# zeta2rework_lw_v19.net
KiCad netlist of a schematic drawn in EAGLE
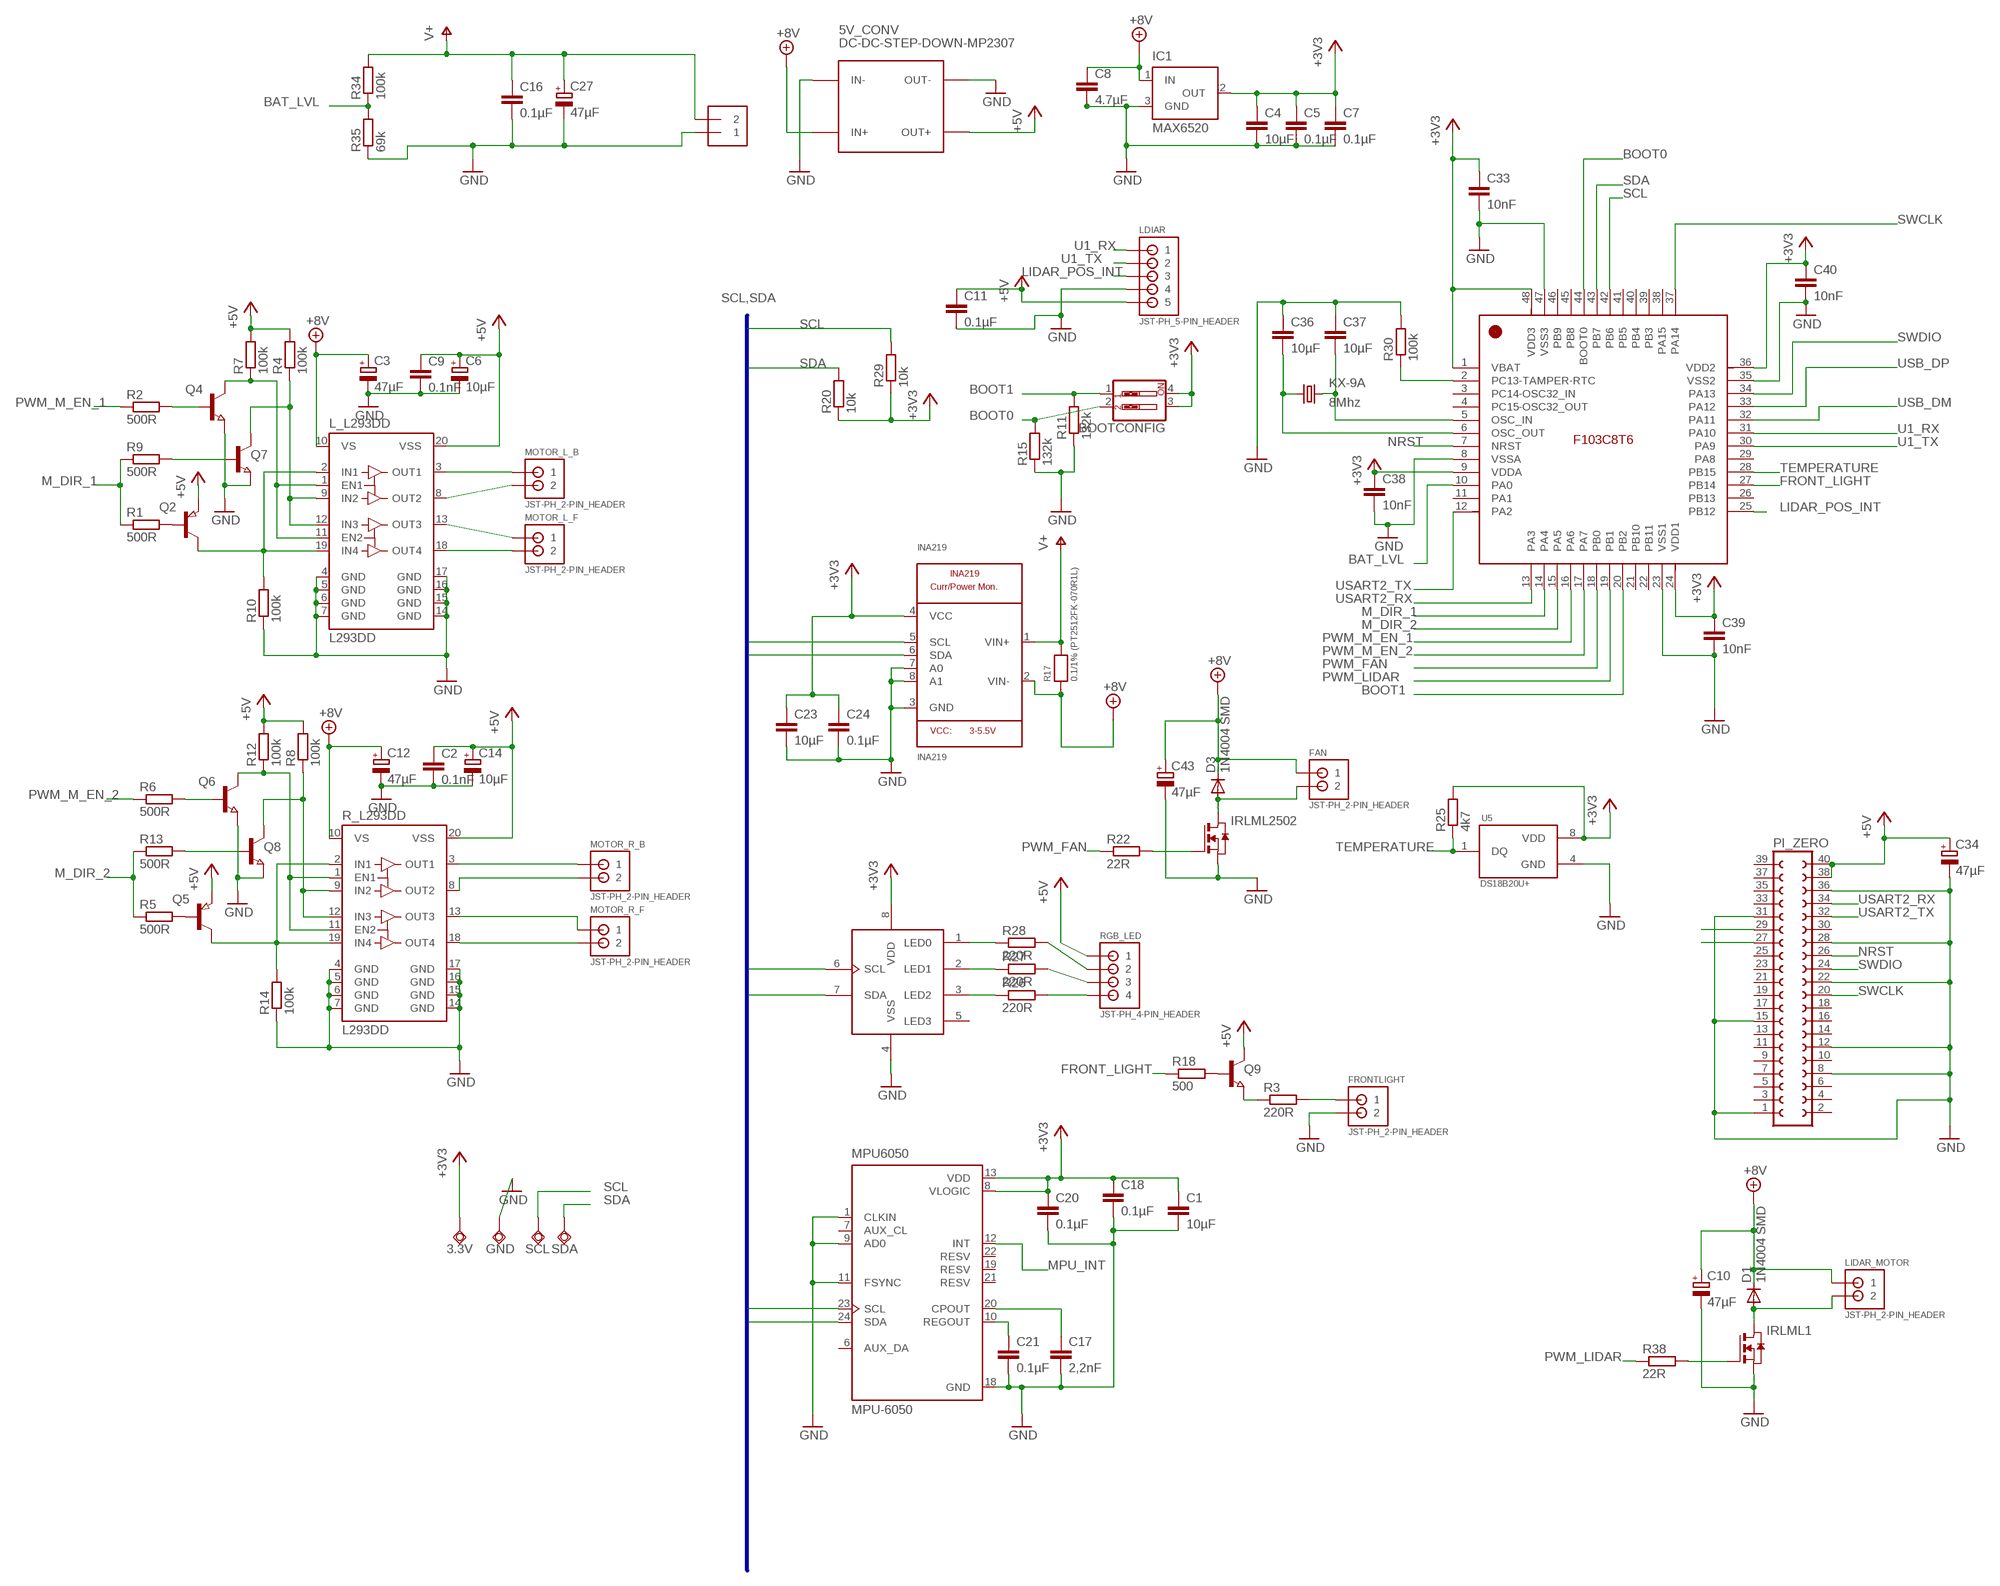
[diagram p0: schematic, sheet 1]

(export (version "E")
  (design (tool "Eeschema 10.0.6"))
  (components
    (comp (ref "3.3V")
      (value "TPSQTP20R")
      (footprint "eagle-import:TP20R")
      (libsource (lib "eagle-import") (part "TPSQTP20R"))
    )
    (comp (ref "5V_CONV")
      (value "DC-DC-STEP-DOWN-MP2307")
      (footprint "eagle-import:DC-DC-STEP-DOWN-MP2307")
      (libsource (lib "eagle-import") (part "DC-DC-STEP-DOWN-MP2307"))
    )
    (comp (ref "BOOTCONFIG")
      (value "SW_DIP-2")
      (footprint "eagle-import:EDG-02")
      (libsource (lib "eagle-import") (part "SW_DIP-2"))
    )
    (comp (ref "C1")
      (value "10µF")
      (footprint "eagle-import:C1206")
      (libsource (lib "eagle-import") (part "C-EUC1206"))
    )
    (comp (ref "C2")
      (value "0.1nF")
      (footprint "eagle-import:C1206")
      (libsource (lib "eagle-import") (part "C-EUC1206"))
    )
    (comp (ref "C3")
      (value "47µF")
      (footprint "eagle-import:UD-4X5,8_NICHICON")
      (libsource (lib "eagle-import") (part "CPOL-EUUD-4X5,8"))
    )
    (comp (ref "C4")
      (value "10µF")
      (footprint "eagle-import:C1206")
      (libsource (lib "eagle-import") (part "C-EUC1206"))
    )
    (comp (ref "C5")
      (value "0.1µF")
      (footprint "eagle-import:C1206")
      (libsource (lib "eagle-import") (part "C-EUC1206"))
    )
    (comp (ref "C6")
      (value "10µF")
      (footprint "eagle-import:UD-4X5,8_NICHICON")
      (libsource (lib "eagle-import") (part "CPOL-EUUD-4X5,8"))
    )
    (comp (ref "C7")
      (value "0.1µF")
      (footprint "eagle-import:C1206")
      (libsource (lib "eagle-import") (part "C-EUC1206"))
    )
    (comp (ref "C8")
      (value "4.7µF")
      (footprint "eagle-import:C1206")
      (libsource (lib "eagle-import") (part "C-EUC1206"))
    )
    (comp (ref "C9")
      (value "0.1nF")
      (footprint "eagle-import:C1206")
      (libsource (lib "eagle-import") (part "C-EUC1206"))
    )
    (comp (ref "C10")
      (value "47µF")
      (footprint "eagle-import:UD-4X5,8_NICHICON")
      (libsource (lib "eagle-import") (part "CPOL-EUUD-4X5,8"))
    )
    (comp (ref "C11")
      (value "0.1µF")
      (footprint "eagle-import:C1206")
      (libsource (lib "eagle-import") (part "C-EUC1206"))
    )
    (comp (ref "C12")
      (value "47µF")
      (footprint "eagle-import:UD-4X5,8_NICHICON")
      (libsource (lib "eagle-import") (part "CPOL-EUUD-4X5,8"))
    )
    (comp (ref "C14")
      (value "10µF")
      (footprint "eagle-import:UD-4X5,8_NICHICON")
      (libsource (lib "eagle-import") (part "CPOL-EUUD-4X5,8"))
    )
    (comp (ref "C16")
      (value "0.1µF")
      (footprint "eagle-import:C1206")
      (libsource (lib "eagle-import") (part "C-EUC1206"))
    )
    (comp (ref "C17")
      (value "2,2nF")
      (footprint "eagle-import:C1206")
      (libsource (lib "eagle-import") (part "C-EUC1206"))
    )
    (comp (ref "C18")
      (value "0.1µF")
      (footprint "eagle-import:C1206")
      (libsource (lib "eagle-import") (part "C-EUC1206"))
    )
    (comp (ref "C20")
      (value "0.1µF")
      (footprint "eagle-import:C1206")
      (libsource (lib "eagle-import") (part "C-EUC1206"))
    )
    (comp (ref "C21")
      (value "0.1µF")
      (footprint "eagle-import:C1206")
      (libsource (lib "eagle-import") (part "C-EUC1206"))
    )
    (comp (ref "C23")
      (value "10µF")
      (footprint "eagle-import:C1206")
      (libsource (lib "eagle-import") (part "C-EUC1206"))
    )
    (comp (ref "C24")
      (value "0.1µF")
      (footprint "eagle-import:C1206")
      (libsource (lib "eagle-import") (part "C-EUC1206"))
    )
    (comp (ref "C27")
      (value "47µF")
      (footprint "eagle-import:UD-4X5,8_NICHICON")
      (libsource (lib "eagle-import") (part "CPOL-EUUD-4X5,8"))
    )
    (comp (ref "C33")
      (value "10nF")
      (footprint "eagle-import:C1206")
      (libsource (lib "eagle-import") (part "C-EUC1206"))
    )
    (comp (ref "C34")
      (value "47µF")
      (footprint "eagle-import:UD-4X5,8_NICHICON")
      (libsource (lib "eagle-import") (part "CPOL-EUUD-4X5,8"))
    )
    (comp (ref "C36")
      (value "10µF")
      (footprint "eagle-import:C1206")
      (libsource (lib "eagle-import") (part "C-EUC1206"))
    )
    (comp (ref "C37")
      (value "10µF")
      (footprint "eagle-import:C1206")
      (libsource (lib "eagle-import") (part "C-EUC1206"))
    )
    (comp (ref "C38")
      (value "10nF")
      (footprint "eagle-import:C1206")
      (libsource (lib "eagle-import") (part "C-EUC1206"))
    )
    (comp (ref "C39")
      (value "10nF")
      (footprint "eagle-import:C1206")
      (libsource (lib "eagle-import") (part "C-EUC1206"))
    )
    (comp (ref "C40")
      (value "10nF")
      (footprint "eagle-import:C1206")
      (libsource (lib "eagle-import") (part "C-EUC1206"))
    )
    (comp (ref "C43")
      (value "47µF")
      (footprint "eagle-import:UD-4X5,8_NICHICON")
      (libsource (lib "eagle-import") (part "CPOL-EUUD-4X5,8"))
    )
    (comp (ref "D1")
      (value "1N4004 SMD")
      (footprint "eagle-import:DO214AC")
      (libsource (lib "eagle-import") (part "DIODE-DO214AC"))
    )
    (comp (ref "D3")
      (value "1N4004 SMD")
      (footprint "eagle-import:DO214AC")
      (libsource (lib "eagle-import") (part "DIODE-DO214AC"))
    )
    (comp (ref "FAN")
      (value "JST-PH_2-PIN_HEADER")
      (footprint "eagle-import:JST_B2B-PH_HEADER")
      (libsource (lib "eagle-import") (part "JST-PH_2-PIN_HEADER"))
    )
    (comp (ref "FRONTLIGHT")
      (value "JST-PH_2-PIN_HEADER")
      (footprint "eagle-import:JST_B2B-PH_HEADER")
      (libsource (lib "eagle-import") (part "JST-PH_2-PIN_HEADER"))
    )
    (comp (ref "GND")
      (value "TPSQTP20R")
      (footprint "eagle-import:TP20R")
      (libsource (lib "eagle-import") (part "TPSQTP20R"))
    )
    (comp (ref "IC1")
      (value "MAX6520")
      (footprint "eagle-import:SOT23")
      (fields (field (name "MF") "MAXIM") (field (name "MPN") "MAX6520EUR-T"))
      (libsource (lib "eagle-import") (part "MAX6520"))
    )
    (comp (ref "INA219")
      (value "INA219")
      (footprint "eagle-import:SOT23-8")
      (fields (field (name "MF") "Texas Instruments"))
      (libsource (lib "eagle-import") (part "INA219"))
    )
    (comp (ref "IRLML1")
      (value "NMOSSOT23")
      (footprint "eagle-import:SOT-23")
      (libsource (lib "eagle-import") (part "NMOSSOT23"))
    )
    (comp (ref "IRLML2502")
      (value "NMOSSOT23")
      (footprint "eagle-import:SOT-23")
      (libsource (lib "eagle-import") (part "NMOSSOT23"))
    )
    (comp (ref "KX-9A")
      (value "8Mhz")
      (footprint "eagle-import:5.0X3.2_KX-9A")
      (libsource (lib "eagle-import") (part "KX-9A"))
    )
    (comp (ref "LDIAR")
      (value "JST-PH_5-PIN_HEADER")
      (footprint "eagle-import:JST_B5B-PH_HEADER")
      (libsource (lib "eagle-import") (part "JST-PH_5-PIN_HEADER"))
    )
    (comp (ref "LIDAR_MOTOR")
      (value "JST-PH_2-PIN_HEADER")
      (footprint "eagle-import:JST_B2B-PH_HEADER")
      (libsource (lib "eagle-import") (part "JST-PH_2-PIN_HEADER"))
    )
    (comp (ref "LIPO_2S")
      (value "TERMBLOCK_1X2-3.5MM")
      (footprint "eagle-import:1X2-3.5MM")
      (libsource (lib "eagle-import") (part "TERMBLOCK_1X2-3.5MM"))
    )
    (comp (ref "L_L293DD")
      (value "L293DD")
      (footprint "eagle-import:SO20")
      (libsource (lib "eagle-import") (part "L293DD"))
    )
    (comp (ref "MOTOR_L_B")
      (value "JST-PH_2-PIN_HEADER")
      (footprint "eagle-import:JST_B2B-PH_HEADER")
      (libsource (lib "eagle-import") (part "JST-PH_2-PIN_HEADER"))
    )
    (comp (ref "MOTOR_L_F")
      (value "JST-PH_2-PIN_HEADER")
      (footprint "eagle-import:JST_B2B-PH_HEADER")
      (libsource (lib "eagle-import") (part "JST-PH_2-PIN_HEADER"))
    )
    (comp (ref "MOTOR_R_B")
      (value "JST-PH_2-PIN_HEADER")
      (footprint "eagle-import:JST_B2B-PH_HEADER")
      (libsource (lib "eagle-import") (part "JST-PH_2-PIN_HEADER"))
    )
    (comp (ref "MOTOR_R_F")
      (value "JST-PH_2-PIN_HEADER")
      (footprint "eagle-import:JST_B2B-PH_HEADER")
      (libsource (lib "eagle-import") (part "JST-PH_2-PIN_HEADER"))
    )
    (comp (ref "MPU6050")
      (value "MPU-6050")
      (footprint "eagle-import:QFN50P400X400X95-24N")
      (fields (field (name "MF") "TDK"))
      (libsource (lib "eagle-import") (part "MPU-6050"))
    )
    (comp (ref "PCA9533")
      (value "PCA9533")
      (footprint "eagle-import:SOIC8")
      (libsource (lib "eagle-import") (part "PCA9533"))
    )
    (comp (ref "PI_ZERO")
      (value "FE20-2")
      (footprint "eagle-import:FE20-2")
      (libsource (lib "eagle-import") (part "FE20-2"))
    )
    (comp (ref "Q2")
      (value "PNP-TRANSISTOR_SOT23")
      (footprint "eagle-import:SOT23")
      (libsource (lib "eagle-import") (part "PNP-TRANSISTOR_SOT23"))
    )
    (comp (ref "Q4")
      (value "NPN-TRANSISTOR_SOT23")
      (footprint "eagle-import:SOT23")
      (libsource (lib "eagle-import") (part "NPN-TRANSISTOR_SOT23"))
    )
    (comp (ref "Q5")
      (value "PNP-TRANSISTOR_SOT23")
      (footprint "eagle-import:SOT23")
      (libsource (lib "eagle-import") (part "PNP-TRANSISTOR_SOT23"))
    )
    (comp (ref "Q6")
      (value "NPN-TRANSISTOR_SOT23")
      (footprint "eagle-import:SOT23")
      (libsource (lib "eagle-import") (part "NPN-TRANSISTOR_SOT23"))
    )
    (comp (ref "Q7")
      (value "NPN-TRANSISTOR_SOT23")
      (footprint "eagle-import:SOT23")
      (libsource (lib "eagle-import") (part "NPN-TRANSISTOR_SOT23"))
    )
    (comp (ref "Q8")
      (value "NPN-TRANSISTOR_SOT23")
      (footprint "eagle-import:SOT23")
      (libsource (lib "eagle-import") (part "NPN-TRANSISTOR_SOT23"))
    )
    (comp (ref "Q9")
      (value "NPN-TRANSISTOR_SOT23")
      (footprint "eagle-import:SOT23")
      (libsource (lib "eagle-import") (part "NPN-TRANSISTOR_SOT23"))
    )
    (comp (ref "R1")
      (value "500R")
      (footprint "eagle-import:R0603")
      (libsource (lib "eagle-import") (part "R-EU_R0603"))
    )
    (comp (ref "R2")
      (value "500R")
      (footprint "eagle-import:R0603")
      (libsource (lib "eagle-import") (part "R-EU_R0603"))
    )
    (comp (ref "R3")
      (value "220R")
      (footprint "eagle-import:R0603")
      (libsource (lib "eagle-import") (part "R-EU_R0603"))
    )
    (comp (ref "R4")
      (value "100k")
      (footprint "eagle-import:R0603")
      (libsource (lib "eagle-import") (part "R-EU_R0603"))
    )
    (comp (ref "R5")
      (value "500R")
      (footprint "eagle-import:R0603")
      (libsource (lib "eagle-import") (part "R-EU_R0603"))
    )
    (comp (ref "R6")
      (value "500R")
      (footprint "eagle-import:R0603")
      (libsource (lib "eagle-import") (part "R-EU_R0603"))
    )
    (comp (ref "R7")
      (value "100k")
      (footprint "eagle-import:R0603")
      (libsource (lib "eagle-import") (part "R-EU_R0603"))
    )
    (comp (ref "R8")
      (value "100k")
      (footprint "eagle-import:R0603")
      (libsource (lib "eagle-import") (part "R-EU_R0603"))
    )
    (comp (ref "R9")
      (value "500R")
      (footprint "eagle-import:R0603")
      (libsource (lib "eagle-import") (part "R-EU_R0603"))
    )
    (comp (ref "R10")
      (value "100k")
      (footprint "eagle-import:R0603")
      (libsource (lib "eagle-import") (part "R-EU_R0603"))
    )
    (comp (ref "R11")
      (value "132k")
      (footprint "eagle-import:R0603")
      (libsource (lib "eagle-import") (part "R-EU_R0603"))
    )
    (comp (ref "R12")
      (value "100k")
      (footprint "eagle-import:R0603")
      (libsource (lib "eagle-import") (part "R-EU_R0603"))
    )
    (comp (ref "R13")
      (value "500R")
      (footprint "eagle-import:R0603")
      (libsource (lib "eagle-import") (part "R-EU_R0603"))
    )
    (comp (ref "R14")
      (value "100k")
      (footprint "eagle-import:R0603")
      (libsource (lib "eagle-import") (part "R-EU_R0603"))
    )
    (comp (ref "R15")
      (value "132k")
      (footprint "eagle-import:R0603")
      (libsource (lib "eagle-import") (part "R-EU_R0603"))
    )
    (comp (ref "R17")
      (value "0.1/1% (PT2512FK-070R1L)")
      (footprint "eagle-import:2512")
      (libsource (lib "eagle-import") (part "RESISTOR2512"))
    )
    (comp (ref "R18")
      (value "500")
      (footprint "eagle-import:R1206")
      (libsource (lib "eagle-import") (part "R-EU_R1206"))
    )
    (comp (ref "R20")
      (value "10k")
      (footprint "eagle-import:R0603")
      (libsource (lib "eagle-import") (part "R-EU_R0603"))
    )
    (comp (ref "R22")
      (value "22R")
      (footprint "eagle-import:R0603")
      (libsource (lib "eagle-import") (part "R-EU_R0603"))
    )
    (comp (ref "R25")
      (value "4k7")
      (footprint "eagle-import:R0603")
      (libsource (lib "eagle-import") (part "R-EU_R0603"))
    )
    (comp (ref "R26")
      (value "220R")
      (footprint "eagle-import:R0603")
      (libsource (lib "eagle-import") (part "R-EU_R0603"))
    )
    (comp (ref "R27")
      (value "220R")
      (footprint "eagle-import:R0603")
      (libsource (lib "eagle-import") (part "R-EU_R0603"))
    )
    (comp (ref "R28")
      (value "220R")
      (footprint "eagle-import:R0603")
      (libsource (lib "eagle-import") (part "R-EU_R0603"))
    )
    (comp (ref "R29")
      (value "10k")
      (footprint "eagle-import:R0603")
      (libsource (lib "eagle-import") (part "R-EU_R0603"))
    )
    (comp (ref "R30")
      (value "100k")
      (footprint "eagle-import:R0603")
      (libsource (lib "eagle-import") (part "R-EU_R0603"))
    )
    (comp (ref "R34")
      (value "100k")
      (footprint "eagle-import:R0603")
      (libsource (lib "eagle-import") (part "R-EU_R0603"))
    )
    (comp (ref "R35")
      (value "69k")
      (footprint "eagle-import:R0603")
      (libsource (lib "eagle-import") (part "R-EU_R0603"))
    )
    (comp (ref "R38")
      (value "22R")
      (footprint "eagle-import:R0603")
      (libsource (lib "eagle-import") (part "R-EU_R0603"))
    )
    (comp (ref "RGB_LED")
      (value "JST-PH_4-PIN_HEADER")
      (footprint "eagle-import:JST_B4B-PH_HEADER")
      (libsource (lib "eagle-import") (part "JST-PH_4-PIN_HEADER"))
    )
    (comp (ref "R_L293DD")
      (value "L293DD")
      (footprint "eagle-import:SO20")
      (libsource (lib "eagle-import") (part "L293DD"))
    )
    (comp (ref "SCL")
      (value "TPSQTP20R")
      (footprint "eagle-import:TP20R")
      (libsource (lib "eagle-import") (part "TPSQTP20R"))
    )
    (comp (ref "SDA")
      (value "TPSQTP20R")
      (footprint "eagle-import:TP20R")
      (libsource (lib "eagle-import") (part "TPSQTP20R"))
    )
    (comp (ref "STM32F103CB")
      (value "STM32F103CB")
      (footprint "eagle-import:LQFP48_7X7MM_0.5MMPP")
      (fields (field (name "MF") "STMicroelectronics") (field (name "MP") "STM32F103C8T6"))
      (libsource (lib "eagle-import") (part "STM32F103C8T6"))
    )
    (comp (ref "U5")
      (value "DS18B20U+")
      (footprint "eagle-import:SOP65P490X95-8N")
      (fields (field (name "MF") "Maxim"))
      (libsource (lib "eagle-import") (part "DS18B20U+"))
    )
  )
  (nets
    (net (code "1") (name "+3V3") (class "Default")
      (node (ref "3.3V") (pin "TP") (pinfunction "TP_TP") (pintype "input"))
      (node (ref "BOOTCONFIG") (pin "3") (pinfunction "3_3") (pintype "passive"))
      (node (ref "BOOTCONFIG") (pin "4") (pinfunction "4_4") (pintype "passive"))
      (node (ref "C1") (pin "1") (pinfunction "1_1") (pintype "passive"))
      (node (ref "C18") (pin "1") (pinfunction "1_1") (pintype "passive"))
      (node (ref "C20") (pin "1") (pinfunction "1_1") (pintype "passive"))
      (node (ref "C23") (pin "1") (pinfunction "1_1") (pintype "passive"))
      (node (ref "C24") (pin "1") (pinfunction "1_1") (pintype "passive"))
      (node (ref "C33") (pin "1") (pinfunction "1_1") (pintype "passive"))
      (node (ref "C38") (pin "1") (pinfunction "1_1") (pintype "passive"))
      (node (ref "C39") (pin "1") (pinfunction "1_1") (pintype "passive"))
      (node (ref "C4") (pin "1") (pinfunction "1_1") (pintype "passive"))
      (node (ref "C40") (pin "1") (pinfunction "1_1") (pintype "passive"))
      (node (ref "C5") (pin "1") (pinfunction "1_1") (pintype "passive"))
      (node (ref "C7") (pin "1") (pinfunction "1_1") (pintype "passive"))
      (node (ref "IC1") (pin "2") (pinfunction "OUT_2") (pintype "output"))
      (node (ref "INA219") (pin "4") (pinfunction "VCC_4") (pintype "bidirectional"))
      (node (ref "MPU6050") (pin "13") (pinfunction "VDD_13") (pintype "power_in"))
      (node (ref "MPU6050") (pin "8") (pinfunction "VLOGIC_8") (pintype "power_in"))
      (node (ref "PCA9533") (pin "8") (pinfunction "VDD_8") (pintype "power_in"))
      (node (ref "R20") (pin "1") (pinfunction "1_1") (pintype "passive"))
      (node (ref "R25") (pin "2") (pinfunction "2_2") (pintype "passive"))
      (node (ref "R29") (pin "1") (pinfunction "1_1") (pintype "passive"))
      (node (ref "STM32F103CB") (pin "1") (pinfunction "VBAT_1") (pintype "bidirectional"))
      (node (ref "STM32F103CB") (pin "24") (pinfunction "VDD1_24") (pintype "bidirectional"))
      (node (ref "STM32F103CB") (pin "36") (pinfunction "VDD2_36") (pintype "bidirectional"))
      (node (ref "STM32F103CB") (pin "48") (pinfunction "VDD3_48") (pintype "bidirectional"))
      (node (ref "STM32F103CB") (pin "9") (pinfunction "VDDA_9") (pintype "bidirectional"))
      (node (ref "U5") (pin "8") (pinfunction "VDD_8") (pintype "power_in"))
    )
    (net (code "2") (name "+5V") (class "Default")
      (node (ref "5V_CONV") (pin "OUT+") (pinfunction "OUT+_OUT+") (pintype "bidirectional"))
      (node (ref "C11") (pin "1") (pinfunction "1_1") (pintype "passive"))
      (node (ref "C14") (pin "+") (pinfunction "+_+") (pintype "passive"))
      (node (ref "C2") (pin "1") (pinfunction "1_1") (pintype "passive"))
      (node (ref "C34") (pin "+") (pinfunction "+_+") (pintype "passive"))
      (node (ref "C6") (pin "+") (pinfunction "+_+") (pintype "passive"))
      (node (ref "C9") (pin "1") (pinfunction "1_1") (pintype "passive"))
      (node (ref "LDIAR") (pin "P5") (pinfunction "5_P5") (pintype "bidirectional"))
      (node (ref "L_L293DD") (pin "20") (pinfunction "VSS_20") (pintype "power_in"))
      (node (ref "PI_ZERO") (pin "38") (pinfunction "38_38") (pintype "passive"))
      (node (ref "PI_ZERO") (pin "40") (pinfunction "40_40") (pintype "passive"))
      (node (ref "Q2") (pin "2") (pinfunction "E_2") (pintype "passive"))
      (node (ref "Q5") (pin "2") (pinfunction "E_2") (pintype "passive"))
      (node (ref "Q9") (pin "3") (pinfunction "C_3") (pintype "passive"))
      (node (ref "R12") (pin "2") (pinfunction "2_2") (pintype "passive"))
      (node (ref "R4") (pin "2") (pinfunction "2_2") (pintype "passive"))
      (node (ref "R7") (pin "2") (pinfunction "2_2") (pintype "passive"))
      (node (ref "R8") (pin "2") (pinfunction "2_2") (pintype "passive"))
      (node (ref "RGB_LED") (pin "P1") (pinfunction "1_P1") (pintype "bidirectional"))
      (node (ref "R_L293DD") (pin "20") (pinfunction "VSS_20") (pintype "power_in"))
    )
    (net (code "3") (name "+8V") (class "Default")
      (node (ref "5V_CONV") (pin "IN+") (pinfunction "IN+_IN+") (pintype "bidirectional"))
      (node (ref "C10") (pin "+") (pinfunction "+_+") (pintype "passive"))
      (node (ref "C12") (pin "+") (pinfunction "+_+") (pintype "passive"))
      (node (ref "C3") (pin "+") (pinfunction "+_+") (pintype "passive"))
      (node (ref "C43") (pin "+") (pinfunction "+_+") (pintype "passive"))
      (node (ref "C8") (pin "1") (pinfunction "1_1") (pintype "passive"))
      (node (ref "D1") (pin "C") (pinfunction "C_C") (pintype "passive"))
      (node (ref "D3") (pin "C") (pinfunction "C_C") (pintype "passive"))
      (node (ref "FAN") (pin "P1") (pinfunction "1_P1") (pintype "bidirectional"))
      (node (ref "IC1") (pin "1") (pinfunction "IN_1") (pintype "input"))
      (node (ref "INA219") (pin "2") (pinfunction "VIN-_2") (pintype "bidirectional"))
      (node (ref "LIDAR_MOTOR") (pin "P1") (pinfunction "1_P1") (pintype "bidirectional"))
      (node (ref "L_L293DD") (pin "10") (pinfunction "VS_10") (pintype "power_in"))
      (node (ref "R17") (pin "1") (pinfunction "1_1") (pintype "passive"))
      (node (ref "R_L293DD") (pin "10") (pinfunction "VS_10") (pintype "power_in"))
    )
    (net (code "4") (name "/BAT_LVL") (class "Default")
      (node (ref "R34") (pin "1") (pinfunction "1_1") (pintype "passive"))
      (node (ref "R35") (pin "2") (pinfunction "2_2") (pintype "passive"))
      (node (ref "STM32F103CB") (pin "10") (pinfunction "PA0_10") (pintype "bidirectional"))
    )
    (net (code "5") (name "/BOOT0") (class "Default")
      (node (ref "BOOTCONFIG") (pin "2") (pinfunction "2_2") (pintype "passive"))
      (node (ref "R15") (pin "2") (pinfunction "2_2") (pintype "passive"))
      (node (ref "STM32F103CB") (pin "44") (pinfunction "BOOT0_44") (pintype "bidirectional"))
    )
    (net (code "6") (name "/BOOT1") (class "Default")
      (node (ref "BOOTCONFIG") (pin "1") (pinfunction "1_1") (pintype "passive"))
      (node (ref "R11") (pin "2") (pinfunction "2_2") (pintype "passive"))
      (node (ref "STM32F103CB") (pin "20") (pinfunction "PB2_20") (pintype "bidirectional"))
    )
    (net (code "7") (name "/FRONT_LIGHT") (class "Default")
      (node (ref "R18") (pin "1") (pinfunction "1_1") (pintype "passive"))
      (node (ref "STM32F103CB") (pin "27") (pinfunction "PB14_27") (pintype "bidirectional"))
    )
    (net (code "8") (name "/LIDAR_POS_INT") (class "Default")
      (node (ref "LDIAR") (pin "P3") (pinfunction "3_P3") (pintype "bidirectional"))
      (node (ref "STM32F103CB") (pin "25") (pinfunction "PB12_25") (pintype "bidirectional"))
    )
    (net (code "9") (name "/MPU_INT") (class "Default")
      (node (ref "MPU6050") (pin "12") (pinfunction "INT_12") (pintype "output"))
    )
    (net (code "10") (name "/M_DIR_1") (class "Default")
      (node (ref "R1") (pin "1") (pinfunction "1_1") (pintype "passive"))
      (node (ref "R9") (pin "1") (pinfunction "1_1") (pintype "passive"))
      (node (ref "STM32F103CB") (pin "14") (pinfunction "PA4_14") (pintype "bidirectional"))
    )
    (net (code "11") (name "/M_DIR_2") (class "Default")
      (node (ref "R13") (pin "1") (pinfunction "1_1") (pintype "passive"))
      (node (ref "R5") (pin "1") (pinfunction "1_1") (pintype "passive"))
      (node (ref "STM32F103CB") (pin "15") (pinfunction "PA5_15") (pintype "bidirectional"))
    )
    (net (code "12") (name "/NRST") (class "Default")
      (node (ref "PI_ZERO") (pin "26") (pinfunction "26_26") (pintype "passive"))
      (node (ref "STM32F103CB") (pin "7") (pinfunction "NRST_7") (pintype "bidirectional"))
    )
    (net (code "13") (name "/PWM_FAN") (class "Default")
      (node (ref "R22") (pin "1") (pinfunction "1_1") (pintype "passive"))
      (node (ref "STM32F103CB") (pin "18") (pinfunction "PB0_18") (pintype "bidirectional"))
    )
    (net (code "14") (name "/PWM_LIDAR") (class "Default")
      (node (ref "R38") (pin "1") (pinfunction "1_1") (pintype "passive"))
      (node (ref "STM32F103CB") (pin "19") (pinfunction "PB1_19") (pintype "bidirectional"))
    )
    (net (code "15") (name "/PWM_M_EN_1") (class "Default")
      (node (ref "R2") (pin "1") (pinfunction "1_1") (pintype "passive"))
      (node (ref "STM32F103CB") (pin "16") (pinfunction "PA6_16") (pintype "bidirectional"))
    )
    (net (code "16") (name "/PWM_M_EN_2") (class "Default")
      (node (ref "R6") (pin "1") (pinfunction "1_1") (pintype "passive"))
      (node (ref "STM32F103CB") (pin "17") (pinfunction "PA7_17") (pintype "bidirectional"))
    )
    (net (code "17") (name "/SCL") (class "Default")
      (node (ref "INA219") (pin "5") (pinfunction "SCL_5") (pintype "bidirectional"))
      (node (ref "MPU6050") (pin "23") (pinfunction "SCL_23") (pintype "input"))
      (node (ref "PCA9533") (pin "6") (pinfunction "SCL_6") (pintype "input"))
      (node (ref "R29") (pin "2") (pinfunction "2_2") (pintype "passive"))
      (node (ref "SCL") (pin "TP") (pinfunction "TP_TP") (pintype "input"))
      (node (ref "STM32F103CB") (pin "42") (pinfunction "PB6_42") (pintype "bidirectional"))
    )
    (net (code "18") (name "/SDA") (class "Default")
      (node (ref "INA219") (pin "6") (pinfunction "SDA_6") (pintype "bidirectional"))
      (node (ref "MPU6050") (pin "24") (pinfunction "SDA_24") (pintype "bidirectional"))
      (node (ref "PCA9533") (pin "7") (pinfunction "SDA_7") (pintype "bidirectional"))
      (node (ref "R20") (pin "2") (pinfunction "2_2") (pintype "passive"))
      (node (ref "SDA") (pin "TP") (pinfunction "TP_TP") (pintype "input"))
      (node (ref "STM32F103CB") (pin "43") (pinfunction "PB7_43") (pintype "bidirectional"))
    )
    (net (code "19") (name "/SWCLK") (class "Default")
      (node (ref "PI_ZERO") (pin "20") (pinfunction "20_20") (pintype "passive"))
      (node (ref "STM32F103CB") (pin "37") (pinfunction "PA14_37") (pintype "bidirectional"))
    )
    (net (code "20") (name "/SWDIO") (class "Default")
      (node (ref "PI_ZERO") (pin "24") (pinfunction "24_24") (pintype "passive"))
      (node (ref "STM32F103CB") (pin "34") (pinfunction "PA13_34") (pintype "bidirectional"))
    )
    (net (code "21") (name "/TEMPERATURE") (class "Default")
      (node (ref "R25") (pin "1") (pinfunction "1_1") (pintype "passive"))
      (node (ref "STM32F103CB") (pin "28") (pinfunction "PB15_28") (pintype "bidirectional"))
      (node (ref "U5") (pin "1") (pinfunction "DQ_1") (pintype "bidirectional"))
    )
    (net (code "22") (name "/U1_RX") (class "Default")
      (node (ref "LDIAR") (pin "P1") (pinfunction "1_P1") (pintype "bidirectional"))
      (node (ref "STM32F103CB") (pin "31") (pinfunction "PA10_31") (pintype "bidirectional"))
    )
    (net (code "23") (name "/U1_TX") (class "Default")
      (node (ref "LDIAR") (pin "P2") (pinfunction "2_P2") (pintype "bidirectional"))
      (node (ref "STM32F103CB") (pin "30") (pinfunction "PA9_30") (pintype "bidirectional"))
    )
    (net (code "24") (name "/USART2_RX") (class "Default")
      (node (ref "PI_ZERO") (pin "34") (pinfunction "34_34") (pintype "passive"))
      (node (ref "STM32F103CB") (pin "13") (pinfunction "PA3_13") (pintype "bidirectional"))
    )
    (net (code "25") (name "/USART2_TX") (class "Default")
      (node (ref "PI_ZERO") (pin "32") (pinfunction "32_32") (pintype "passive"))
      (node (ref "STM32F103CB") (pin "12") (pinfunction "PA2_12") (pintype "bidirectional"))
    )
    (net (code "26") (name "/USB_DM") (class "Default")
      (node (ref "STM32F103CB") (pin "32") (pinfunction "PA11_32") (pintype "bidirectional"))
    )
    (net (code "27") (name "/USB_DP") (class "Default")
      (node (ref "STM32F103CB") (pin "33") (pinfunction "PA12_33") (pintype "bidirectional"))
    )
    (net (code "29") (name "GND") (class "Default")
      (node (ref "5V_CONV") (pin "IN-") (pinfunction "IN-_IN-") (pintype "bidirectional"))
      (node (ref "5V_CONV") (pin "OUT-") (pinfunction "OUT-_OUT-") (pintype "bidirectional"))
      (node (ref "C1") (pin "2") (pinfunction "2_2") (pintype "passive"))
      (node (ref "C10") (pin "-") (pinfunction "-_-") (pintype "passive"))
      (node (ref "C11") (pin "2") (pinfunction "2_2") (pintype "passive"))
      (node (ref "C12") (pin "-") (pinfunction "-_-") (pintype "passive"))
      (node (ref "C14") (pin "-") (pinfunction "-_-") (pintype "passive"))
      (node (ref "C16") (pin "2") (pinfunction "2_2") (pintype "passive"))
      (node (ref "C17") (pin "2") (pinfunction "2_2") (pintype "passive"))
      (node (ref "C18") (pin "2") (pinfunction "2_2") (pintype "passive"))
      (node (ref "C2") (pin "2") (pinfunction "2_2") (pintype "passive"))
      (node (ref "C20") (pin "2") (pinfunction "2_2") (pintype "passive"))
      (node (ref "C21") (pin "2") (pinfunction "2_2") (pintype "passive"))
      (node (ref "C23") (pin "2") (pinfunction "2_2") (pintype "passive"))
      (node (ref "C24") (pin "2") (pinfunction "2_2") (pintype "passive"))
      (node (ref "C27") (pin "-") (pinfunction "-_-") (pintype "passive"))
      (node (ref "C3") (pin "-") (pinfunction "-_-") (pintype "passive"))
      (node (ref "C33") (pin "2") (pinfunction "2_2") (pintype "passive"))
      (node (ref "C34") (pin "-") (pinfunction "-_-") (pintype "passive"))
      (node (ref "C36") (pin "1") (pinfunction "1_1") (pintype "passive"))
      (node (ref "C37") (pin "1") (pinfunction "1_1") (pintype "passive"))
      (node (ref "C38") (pin "2") (pinfunction "2_2") (pintype "passive"))
      (node (ref "C39") (pin "2") (pinfunction "2_2") (pintype "passive"))
      (node (ref "C4") (pin "2") (pinfunction "2_2") (pintype "passive"))
      (node (ref "C40") (pin "2") (pinfunction "2_2") (pintype "passive"))
      (node (ref "C43") (pin "-") (pinfunction "-_-") (pintype "passive"))
      (node (ref "C5") (pin "2") (pinfunction "2_2") (pintype "passive"))
      (node (ref "C6") (pin "-") (pinfunction "-_-") (pintype "passive"))
      (node (ref "C7") (pin "2") (pinfunction "2_2") (pintype "passive"))
      (node (ref "C8") (pin "2") (pinfunction "2_2") (pintype "passive"))
      (node (ref "C9") (pin "2") (pinfunction "2_2") (pintype "passive"))
      (node (ref "FRONTLIGHT") (pin "P2") (pinfunction "2_P2") (pintype "bidirectional"))
      (node (ref "GND") (pin "TP") (pinfunction "TP_TP") (pintype "input"))
      (node (ref "IC1") (pin "3") (pinfunction "GND_3") (pintype "power_in"))
      (node (ref "INA219") (pin "3") (pinfunction "GND_3") (pintype "bidirectional"))
      (node (ref "INA219") (pin "7") (pinfunction "A0_7") (pintype "bidirectional"))
      (node (ref "INA219") (pin "8") (pinfunction "A1_8") (pintype "bidirectional"))
      (node (ref "IRLML1") (pin "2") (pinfunction "S_2") (pintype "passive"))
      (node (ref "IRLML2502") (pin "2") (pinfunction "S_2") (pintype "passive"))
      (node (ref "LDIAR") (pin "P4") (pinfunction "4_P4") (pintype "bidirectional"))
      (node (ref "LIPO_2S") (pin "1") (pinfunction "1_1") (pintype "passive"))
      (node (ref "L_L293DD") (pin "14") (pinfunction "GND_14") (pintype "power_in"))
      (node (ref "L_L293DD") (pin "15") (pinfunction "GND_15") (pintype "power_in"))
      (node (ref "L_L293DD") (pin "16") (pinfunction "GND_16") (pintype "power_in"))
      (node (ref "L_L293DD") (pin "17") (pinfunction "GND_17") (pintype "power_in"))
      (node (ref "L_L293DD") (pin "4") (pinfunction "GND_4") (pintype "power_in"))
      (node (ref "L_L293DD") (pin "5") (pinfunction "GND_5") (pintype "power_in"))
      (node (ref "L_L293DD") (pin "6") (pinfunction "GND_6") (pintype "power_in"))
      (node (ref "L_L293DD") (pin "7") (pinfunction "GND_7") (pintype "power_in"))
      (node (ref "MPU6050") (pin "1") (pinfunction "CLKIN_1") (pintype "input"))
      (node (ref "MPU6050") (pin "11") (pinfunction "FSYNC_11") (pintype "input"))
      (node (ref "MPU6050") (pin "18") (pinfunction "GND_18") (pintype "power_in"))
      (node (ref "MPU6050") (pin "9") (pinfunction "AD0_9") (pintype "input"))
      (node (ref "PCA9533") (pin "4") (pinfunction "VSS_4") (pintype "power_in"))
      (node (ref "PI_ZERO") (pin "1") (pinfunction "1_1") (pintype "passive"))
      (node (ref "PI_ZERO") (pin "12") (pinfunction "12_12") (pintype "passive"))
      (node (ref "PI_ZERO") (pin "15") (pinfunction "15_15") (pintype "passive"))
      (node (ref "PI_ZERO") (pin "22") (pinfunction "22_22") (pintype "passive"))
      (node (ref "PI_ZERO") (pin "28") (pinfunction "28_28") (pintype "passive"))
      (node (ref "PI_ZERO") (pin "31") (pinfunction "31_31") (pintype "passive"))
      (node (ref "PI_ZERO") (pin "36") (pinfunction "36_36") (pintype "passive"))
      (node (ref "PI_ZERO") (pin "8") (pinfunction "8_8") (pintype "passive"))
      (node (ref "Q4") (pin "2") (pinfunction "E_2") (pintype "passive"))
      (node (ref "Q6") (pin "2") (pinfunction "E_2") (pintype "passive"))
      (node (ref "Q7") (pin "2") (pinfunction "E_2") (pintype "passive"))
      (node (ref "Q8") (pin "2") (pinfunction "E_2") (pintype "passive"))
      (node (ref "R10") (pin "1") (pinfunction "1_1") (pintype "passive"))
      (node (ref "R11") (pin "1") (pinfunction "1_1") (pintype "passive"))
      (node (ref "R14") (pin "1") (pinfunction "1_1") (pintype "passive"))
      (node (ref "R15") (pin "1") (pinfunction "1_1") (pintype "passive"))
      (node (ref "R30") (pin "2") (pinfunction "2_2") (pintype "passive"))
      (node (ref "R35") (pin "1") (pinfunction "1_1") (pintype "passive"))
      (node (ref "R_L293DD") (pin "14") (pinfunction "GND_14") (pintype "power_in"))
      (node (ref "R_L293DD") (pin "15") (pinfunction "GND_15") (pintype "power_in"))
      (node (ref "R_L293DD") (pin "16") (pinfunction "GND_16") (pintype "power_in"))
      (node (ref "R_L293DD") (pin "17") (pinfunction "GND_17") (pintype "power_in"))
      (node (ref "R_L293DD") (pin "4") (pinfunction "GND_4") (pintype "power_in"))
      (node (ref "R_L293DD") (pin "5") (pinfunction "GND_5") (pintype "power_in"))
      (node (ref "R_L293DD") (pin "6") (pinfunction "GND_6") (pintype "power_in"))
      (node (ref "R_L293DD") (pin "7") (pinfunction "GND_7") (pintype "power_in"))
      (node (ref "STM32F103CB") (pin "23") (pinfunction "VSS1_23") (pintype "bidirectional"))
      (node (ref "STM32F103CB") (pin "35") (pinfunction "VSS2_35") (pintype "bidirectional"))
      (node (ref "STM32F103CB") (pin "47") (pinfunction "VSS3_47") (pintype "bidirectional"))
      (node (ref "STM32F103CB") (pin "8") (pinfunction "VSSA_8") (pintype "bidirectional"))
      (node (ref "U5") (pin "4") (pinfunction "GND_4") (pintype "power_in"))
    )
    (net (code "30") (name "Net-(FAN-2)") (class "Default")
      (node (ref "D3") (pin "A") (pinfunction "A_A") (pintype "passive"))
      (node (ref "FAN") (pin "P2") (pinfunction "2_P2") (pintype "bidirectional"))
      (node (ref "IRLML2502") (pin "1") (pinfunction "D_1") (pintype "passive"))
    )
    (net (code "31") (name "Net-(FRONTLIGHT-1)") (class "Default")
      (node (ref "FRONTLIGHT") (pin "P1") (pinfunction "1_P1") (pintype "bidirectional"))
      (node (ref "R3") (pin "2") (pinfunction "2_2") (pintype "passive"))
    )
    (net (code "32") (name "Net-(IRLML1-D)") (class "Default")
      (node (ref "D1") (pin "A") (pinfunction "A_A") (pintype "passive"))
      (node (ref "IRLML1") (pin "1") (pinfunction "D_1") (pintype "passive"))
      (node (ref "LIDAR_MOTOR") (pin "P2") (pinfunction "2_P2") (pintype "bidirectional"))
    )
    (net (code "33") (name "Net-(IRLML1-G)") (class "Default")
      (node (ref "IRLML1") (pin "3") (pinfunction "G_3") (pintype "passive"))
      (node (ref "R38") (pin "2") (pinfunction "2_2") (pintype "passive"))
    )
    (net (code "34") (name "Net-(IRLML2502-G)") (class "Default")
      (node (ref "IRLML2502") (pin "3") (pinfunction "G_3") (pintype "passive"))
      (node (ref "R22") (pin "2") (pinfunction "2_2") (pintype "passive"))
    )
    (net (code "35") (name "Net-(KX-9A-2)") (class "Default")
      (node (ref "C37") (pin "2") (pinfunction "2_2") (pintype "passive"))
      (node (ref "KX-9A") (pin "3") (pinfunction "2_3") (pintype "passive"))
      (node (ref "STM32F103CB") (pin "5") (pinfunction "OSC_IN_5") (pintype "bidirectional"))
    )
    (net (code "36") (name "Net-(L_L293DD-EN1)") (class "Default")
      (node (ref "L_L293DD") (pin "1") (pinfunction "EN1_1") (pintype "input"))
      (node (ref "L_L293DD") (pin "11") (pinfunction "EN2_11") (pintype "input"))
      (node (ref "Q4") (pin "3") (pinfunction "C_3") (pintype "passive"))
      (node (ref "R7") (pin "1") (pinfunction "1_1") (pintype "passive"))
    )
    (net (code "37") (name "Net-(L_L293DD-IN1)") (class "Default")
      (node (ref "L_L293DD") (pin "19") (pinfunction "IN4_19") (pintype "input"))
      (node (ref "L_L293DD") (pin "2") (pinfunction "IN1_2") (pintype "input"))
      (node (ref "Q2") (pin "3") (pinfunction "C_3") (pintype "passive"))
      (node (ref "R10") (pin "2") (pinfunction "2_2") (pintype "passive"))
    )
    (net (code "38") (name "Net-(L_L293DD-IN2)") (class "Default")
      (node (ref "L_L293DD") (pin "12") (pinfunction "IN3_12") (pintype "input"))
      (node (ref "L_L293DD") (pin "9") (pinfunction "IN2_9") (pintype "input"))
      (node (ref "Q7") (pin "3") (pinfunction "C_3") (pintype "passive"))
      (node (ref "R4") (pin "1") (pinfunction "1_1") (pintype "passive"))
    )
    (net (code "39") (name "Net-(L_L293DD-OUT1)") (class "Default")
      (node (ref "L_L293DD") (pin "3") (pinfunction "OUT1_3") (pintype "output"))
      (node (ref "MOTOR_L_B") (pin "P1") (pinfunction "1_P1") (pintype "bidirectional"))
    )
    (net (code "40") (name "Net-(L_L293DD-OUT2)") (class "Default")
      (node (ref "L_L293DD") (pin "8") (pinfunction "OUT2_8") (pintype "output"))
      (node (ref "MOTOR_L_B") (pin "P2") (pinfunction "2_P2") (pintype "bidirectional"))
    )
    (net (code "41") (name "Net-(L_L293DD-OUT3)") (class "Default")
      (node (ref "L_L293DD") (pin "13") (pinfunction "OUT3_13") (pintype "output"))
      (node (ref "MOTOR_L_F") (pin "P1") (pinfunction "1_P1") (pintype "bidirectional"))
    )
    (net (code "42") (name "Net-(L_L293DD-OUT4)") (class "Default")
      (node (ref "L_L293DD") (pin "18") (pinfunction "OUT4_18") (pintype "output"))
      (node (ref "MOTOR_L_F") (pin "P2") (pinfunction "2_P2") (pintype "bidirectional"))
    )
    (net (code "43") (name "Net-(MOTOR_R_B-1)") (class "Default")
      (node (ref "MOTOR_R_B") (pin "P1") (pinfunction "1_P1") (pintype "bidirectional"))
      (node (ref "R_L293DD") (pin "3") (pinfunction "OUT1_3") (pintype "output"))
    )
    (net (code "44") (name "Net-(MOTOR_R_B-2)") (class "Default")
      (node (ref "MOTOR_R_B") (pin "P2") (pinfunction "2_P2") (pintype "bidirectional"))
      (node (ref "R_L293DD") (pin "8") (pinfunction "OUT2_8") (pintype "output"))
    )
    (net (code "45") (name "Net-(MOTOR_R_F-1)") (class "Default")
      (node (ref "MOTOR_R_F") (pin "P1") (pinfunction "1_P1") (pintype "bidirectional"))
      (node (ref "R_L293DD") (pin "13") (pinfunction "OUT3_13") (pintype "output"))
    )
    (net (code "46") (name "Net-(MOTOR_R_F-2)") (class "Default")
      (node (ref "MOTOR_R_F") (pin "P2") (pinfunction "2_P2") (pintype "bidirectional"))
      (node (ref "R_L293DD") (pin "18") (pinfunction "OUT4_18") (pintype "output"))
    )
    (net (code "47") (name "Net-(MPU6050-CPOUT)") (class "Default")
      (node (ref "C17") (pin "1") (pinfunction "1_1") (pintype "passive"))
      (node (ref "MPU6050") (pin "20") (pinfunction "CPOUT_20") (pintype "passive"))
    )
    (net (code "48") (name "Net-(MPU6050-REGOUT)") (class "Default")
      (node (ref "C21") (pin "1") (pinfunction "1_1") (pintype "passive"))
      (node (ref "MPU6050") (pin "10") (pinfunction "REGOUT_10") (pintype "passive"))
    )
    (net (code "49") (name "Net-(PCA9533-LED0)") (class "Default")
      (node (ref "PCA9533") (pin "1") (pinfunction "LED0_1") (pintype "bidirectional"))
      (node (ref "R28") (pin "1") (pinfunction "1_1") (pintype "passive"))
    )
    (net (code "50") (name "Net-(PCA9533-LED1)") (class "Default")
      (node (ref "PCA9533") (pin "2") (pinfunction "LED1_2") (pintype "bidirectional"))
      (node (ref "R27") (pin "1") (pinfunction "1_1") (pintype "passive"))
    )
    (net (code "51") (name "Net-(PCA9533-LED2)") (class "Default")
      (node (ref "PCA9533") (pin "3") (pinfunction "LED2_3") (pintype "bidirectional"))
      (node (ref "R26") (pin "1") (pinfunction "1_1") (pintype "passive"))
    )
    (net (code "52") (name "Net-(Q2-B)") (class "Default")
      (node (ref "Q2") (pin "1") (pinfunction "B_1") (pintype "passive"))
      (node (ref "R1") (pin "2") (pinfunction "2_2") (pintype "passive"))
    )
    (net (code "53") (name "Net-(Q4-B)") (class "Default")
      (node (ref "Q4") (pin "1") (pinfunction "B_1") (pintype "passive"))
      (node (ref "R2") (pin "2") (pinfunction "2_2") (pintype "passive"))
    )
    (net (code "54") (name "Net-(Q5-B)") (class "Default")
      (node (ref "Q5") (pin "1") (pinfunction "B_1") (pintype "passive"))
      (node (ref "R5") (pin "2") (pinfunction "2_2") (pintype "passive"))
    )
    (net (code "55") (name "Net-(Q5-C)") (class "Default")
      (node (ref "Q5") (pin "3") (pinfunction "C_3") (pintype "passive"))
      (node (ref "R14") (pin "2") (pinfunction "2_2") (pintype "passive"))
      (node (ref "R_L293DD") (pin "19") (pinfunction "IN4_19") (pintype "input"))
      (node (ref "R_L293DD") (pin "2") (pinfunction "IN1_2") (pintype "input"))
    )
    (net (code "56") (name "Net-(Q6-B)") (class "Default")
      (node (ref "Q6") (pin "1") (pinfunction "B_1") (pintype "passive"))
      (node (ref "R6") (pin "2") (pinfunction "2_2") (pintype "passive"))
    )
    (net (code "57") (name "Net-(Q6-C)") (class "Default")
      (node (ref "Q6") (pin "3") (pinfunction "C_3") (pintype "passive"))
      (node (ref "R12") (pin "1") (pinfunction "1_1") (pintype "passive"))
      (node (ref "R_L293DD") (pin "1") (pinfunction "EN1_1") (pintype "input"))
      (node (ref "R_L293DD") (pin "11") (pinfunction "EN2_11") (pintype "input"))
    )
    (net (code "58") (name "Net-(Q7-B)") (class "Default")
      (node (ref "Q7") (pin "1") (pinfunction "B_1") (pintype "passive"))
      (node (ref "R9") (pin "2") (pinfunction "2_2") (pintype "passive"))
    )
    (net (code "59") (name "Net-(Q8-B)") (class "Default")
      (node (ref "Q8") (pin "1") (pinfunction "B_1") (pintype "passive"))
      (node (ref "R13") (pin "2") (pinfunction "2_2") (pintype "passive"))
    )
    (net (code "60") (name "Net-(Q8-C)") (class "Default")
      (node (ref "Q8") (pin "3") (pinfunction "C_3") (pintype "passive"))
      (node (ref "R8") (pin "1") (pinfunction "1_1") (pintype "passive"))
      (node (ref "R_L293DD") (pin "12") (pinfunction "IN3_12") (pintype "input"))
      (node (ref "R_L293DD") (pin "9") (pinfunction "IN2_9") (pintype "input"))
    )
    (net (code "61") (name "Net-(Q9-B)") (class "Default")
      (node (ref "Q9") (pin "1") (pinfunction "B_1") (pintype "passive"))
      (node (ref "R18") (pin "2") (pinfunction "2_2") (pintype "passive"))
    )
    (net (code "62") (name "Net-(Q9-E)") (class "Default")
      (node (ref "Q9") (pin "2") (pinfunction "E_2") (pintype "passive"))
      (node (ref "R3") (pin "1") (pinfunction "1_1") (pintype "passive"))
    )
    (net (code "63") (name "Net-(RGB_LED-2)") (class "Default")
      (node (ref "R28") (pin "2") (pinfunction "2_2") (pintype "passive"))
      (node (ref "RGB_LED") (pin "P2") (pinfunction "2_P2") (pintype "bidirectional"))
    )
    (net (code "64") (name "Net-(RGB_LED-3)") (class "Default")
      (node (ref "R27") (pin "2") (pinfunction "2_2") (pintype "passive"))
      (node (ref "RGB_LED") (pin "P3") (pinfunction "3_P3") (pintype "bidirectional"))
    )
    (net (code "65") (name "Net-(RGB_LED-4)") (class "Default")
      (node (ref "R26") (pin "2") (pinfunction "2_2") (pintype "passive"))
      (node (ref "RGB_LED") (pin "P4") (pinfunction "4_P4") (pintype "bidirectional"))
    )
    (net (code "66") (name "Net-(STM32F103CB-OSC_OUT)") (class "Default")
      (node (ref "C36") (pin "2") (pinfunction "2_2") (pintype "passive"))
      (node (ref "KX-9A") (pin "1") (pinfunction "1_1") (pintype "passive"))
      (node (ref "STM32F103CB") (pin "6") (pinfunction "OSC_OUT_6") (pintype "bidirectional"))
    )
    (net (code "67") (name "Net-(STM32F103CB-PC13-TAMPER-RTC)") (class "Default")
      (node (ref "R30") (pin "1") (pinfunction "1_1") (pintype "passive"))
      (node (ref "STM32F103CB") (pin "2") (pinfunction "PC13-TAMPER-RTC_2") (pintype "bidirectional"))
    )
    (net (code "68") (name "V+") (class "Default")
      (node (ref "C16") (pin "1") (pinfunction "1_1") (pintype "passive"))
      (node (ref "C27") (pin "+") (pinfunction "+_+") (pintype "passive"))
      (node (ref "INA219") (pin "1") (pinfunction "VIN+_1") (pintype "bidirectional"))
      (node (ref "LIPO_2S") (pin "2") (pinfunction "2_2") (pintype "passive"))
      (node (ref "R17") (pin "2") (pinfunction "2_2") (pintype "passive"))
      (node (ref "R34") (pin "2") (pinfunction "2_2") (pintype "passive"))
    )
    (net (code "69") (name "unconnected-(MPU6050-AUX_CL-Pad7)") (class "Default")
      (node (ref "MPU6050") (pin "7") (pinfunction "AUX_CL_7") (pintype "input"))
    )
    (net (code "70") (name "unconnected-(MPU6050-AUX_DA-Pad6)") (class "Default")
      (node (ref "MPU6050") (pin "6") (pinfunction "AUX_DA_6") (pintype "bidirectional"))
    )
    (net (code "71") (name "unconnected-(MPU6050-RESV-Pad19)") (class "Default")
      (node (ref "MPU6050") (pin "19") (pinfunction "RESV_19") (pintype "passive"))
    )
    (net (code "72") (name "unconnected-(MPU6050-RESV-Pad21)") (class "Default")
      (node (ref "MPU6050") (pin "21") (pinfunction "RESV_21") (pintype "passive"))
    )
    (net (code "73") (name "unconnected-(MPU6050-RESV-Pad22)") (class "Default")
      (node (ref "MPU6050") (pin "22") (pinfunction "RESV_22") (pintype "passive"))
    )
    (net (code "74") (name "unconnected-(PCA9533-LED3-Pad5)") (class "Default")
      (node (ref "PCA9533") (pin "5") (pinfunction "LED3_5") (pintype "bidirectional"))
    )
    (net (code "75") (name "unconnected-(PI_ZERO-Pad2)") (class "Default")
      (node (ref "PI_ZERO") (pin "2") (pinfunction "2_2") (pintype "passive"))
    )
    (net (code "76") (name "unconnected-(PI_ZERO-Pad3)") (class "Default")
      (node (ref "PI_ZERO") (pin "3") (pinfunction "3_3") (pintype "passive"))
    )
    (net (code "77") (name "unconnected-(PI_ZERO-Pad4)") (class "Default")
      (node (ref "PI_ZERO") (pin "4") (pinfunction "4_4") (pintype "passive"))
    )
    (net (code "78") (name "unconnected-(PI_ZERO-Pad5)") (class "Default")
      (node (ref "PI_ZERO") (pin "5") (pinfunction "5_5") (pintype "passive"))
    )
    (net (code "79") (name "unconnected-(PI_ZERO-Pad6)") (class "Default")
      (node (ref "PI_ZERO") (pin "6") (pinfunction "6_6") (pintype "passive"))
    )
    (net (code "80") (name "unconnected-(PI_ZERO-Pad7)") (class "Default")
      (node (ref "PI_ZERO") (pin "7") (pinfunction "7_7") (pintype "passive"))
    )
    (net (code "81") (name "unconnected-(PI_ZERO-Pad9)") (class "Default")
      (node (ref "PI_ZERO") (pin "9") (pinfunction "9_9") (pintype "passive"))
    )
    (net (code "82") (name "unconnected-(PI_ZERO-Pad10)") (class "Default")
      (node (ref "PI_ZERO") (pin "10") (pinfunction "10_10") (pintype "passive"))
    )
    (net (code "83") (name "unconnected-(PI_ZERO-Pad11)") (class "Default")
      (node (ref "PI_ZERO") (pin "11") (pinfunction "11_11") (pintype "passive"))
    )
    (net (code "84") (name "unconnected-(PI_ZERO-Pad13)") (class "Default")
      (node (ref "PI_ZERO") (pin "13") (pinfunction "13_13") (pintype "passive"))
    )
    (net (code "85") (name "unconnected-(PI_ZERO-Pad14)") (class "Default")
      (node (ref "PI_ZERO") (pin "14") (pinfunction "14_14") (pintype "passive"))
    )
    (net (code "86") (name "unconnected-(PI_ZERO-Pad16)") (class "Default")
      (node (ref "PI_ZERO") (pin "16") (pinfunction "16_16") (pintype "passive"))
    )
    (net (code "87") (name "unconnected-(PI_ZERO-Pad17)") (class "Default")
      (node (ref "PI_ZERO") (pin "17") (pinfunction "17_17") (pintype "passive"))
    )
    (net (code "88") (name "unconnected-(PI_ZERO-Pad18)") (class "Default")
      (node (ref "PI_ZERO") (pin "18") (pinfunction "18_18") (pintype "passive"))
    )
    (net (code "89") (name "unconnected-(PI_ZERO-Pad19)") (class "Default")
      (node (ref "PI_ZERO") (pin "19") (pinfunction "19_19") (pintype "passive"))
    )
    (net (code "90") (name "unconnected-(PI_ZERO-Pad21)") (class "Default")
      (node (ref "PI_ZERO") (pin "21") (pinfunction "21_21") (pintype "passive"))
    )
    (net (code "91") (name "unconnected-(PI_ZERO-Pad23)") (class "Default")
      (node (ref "PI_ZERO") (pin "23") (pinfunction "23_23") (pintype "passive"))
    )
    (net (code "92") (name "unconnected-(PI_ZERO-Pad25)") (class "Default")
      (node (ref "PI_ZERO") (pin "25") (pinfunction "25_25") (pintype "passive"))
    )
    (net (code "93") (name "unconnected-(PI_ZERO-Pad27)") (class "Default")
      (node (ref "PI_ZERO") (pin "27") (pinfunction "27_27") (pintype "passive"))
    )
    (net (code "94") (name "unconnected-(PI_ZERO-Pad29)") (class "Default")
      (node (ref "PI_ZERO") (pin "29") (pinfunction "29_29") (pintype "passive"))
    )
    (net (code "95") (name "unconnected-(PI_ZERO-Pad30)") (class "Default")
      (node (ref "PI_ZERO") (pin "30") (pinfunction "30_30") (pintype "passive"))
    )
    (net (code "96") (name "unconnected-(PI_ZERO-Pad33)") (class "Default")
      (node (ref "PI_ZERO") (pin "33") (pinfunction "33_33") (pintype "passive"))
    )
    (net (code "97") (name "unconnected-(PI_ZERO-Pad35)") (class "Default")
      (node (ref "PI_ZERO") (pin "35") (pinfunction "35_35") (pintype "passive"))
    )
    (net (code "98") (name "unconnected-(PI_ZERO-Pad37)") (class "Default")
      (node (ref "PI_ZERO") (pin "37") (pinfunction "37_37") (pintype "passive"))
    )
    (net (code "99") (name "unconnected-(PI_ZERO-Pad39)") (class "Default")
      (node (ref "PI_ZERO") (pin "39") (pinfunction "39_39") (pintype "passive"))
    )
    (net (code "100") (name "unconnected-(STM32F103CB-PA1-Pad11)") (class "Default")
      (node (ref "STM32F103CB") (pin "11") (pinfunction "PA1_11") (pintype "bidirectional"))
    )
    (net (code "101") (name "unconnected-(STM32F103CB-PA8-Pad29)") (class "Default")
      (node (ref "STM32F103CB") (pin "29") (pinfunction "PA8_29") (pintype "bidirectional"))
    )
    (net (code "102") (name "unconnected-(STM32F103CB-PA15-Pad38)") (class "Default")
      (node (ref "STM32F103CB") (pin "38") (pinfunction "PA15_38") (pintype "bidirectional"))
    )
    (net (code "103") (name "unconnected-(STM32F103CB-PB3-Pad39)") (class "Default")
      (node (ref "STM32F103CB") (pin "39") (pinfunction "PB3_39") (pintype "bidirectional"))
    )
    (net (code "104") (name "unconnected-(STM32F103CB-PB4-Pad40)") (class "Default")
      (node (ref "STM32F103CB") (pin "40") (pinfunction "PB4_40") (pintype "bidirectional"))
    )
    (net (code "105") (name "unconnected-(STM32F103CB-PB5-Pad41)") (class "Default")
      (node (ref "STM32F103CB") (pin "41") (pinfunction "PB5_41") (pintype "bidirectional"))
    )
    (net (code "106") (name "unconnected-(STM32F103CB-PB8-Pad45)") (class "Default")
      (node (ref "STM32F103CB") (pin "45") (pinfunction "PB8_45") (pintype "bidirectional"))
    )
    (net (code "107") (name "unconnected-(STM32F103CB-PB9-Pad46)") (class "Default")
      (node (ref "STM32F103CB") (pin "46") (pinfunction "PB9_46") (pintype "bidirectional"))
    )
    (net (code "108") (name "unconnected-(STM32F103CB-PB10-Pad21)") (class "Default")
      (node (ref "STM32F103CB") (pin "21") (pinfunction "PB10_21") (pintype "bidirectional"))
    )
    (net (code "109") (name "unconnected-(STM32F103CB-PB11-Pad22)") (class "Default")
      (node (ref "STM32F103CB") (pin "22") (pinfunction "PB11_22") (pintype "bidirectional"))
    )
    (net (code "110") (name "unconnected-(STM32F103CB-PB13-Pad26)") (class "Default")
      (node (ref "STM32F103CB") (pin "26") (pinfunction "PB13_26") (pintype "bidirectional"))
    )
    (net (code "111") (name "unconnected-(STM32F103CB-PC14-OSC32_IN-Pad3)") (class "Default")
      (node (ref "STM32F103CB") (pin "3") (pinfunction "PC14-OSC32_IN_3") (pintype "bidirectional"))
    )
    (net (code "112") (name "unconnected-(STM32F103CB-PC15-OSC32_OUT-Pad4)") (class "Default")
      (node (ref "STM32F103CB") (pin "4") (pinfunction "PC15-OSC32_OUT_4") (pintype "bidirectional"))
    )
  )
)
